# scary_rubber.net
KiCad netlist of a schematic drawn in EAGLE
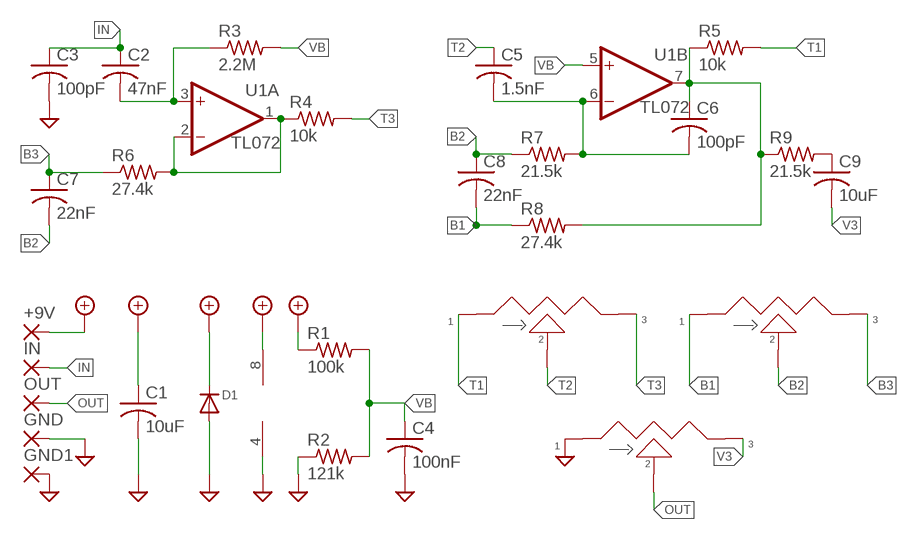
[diagram p0: schematic, sheet 1]

(export (version "E")
  (design (tool "Eeschema 10.0.6"))
  (components
    (comp (ref "+9V")
      (value "SMD2")
      (footprint "eagle-import:SMD1,27-2,54")
      (libsource (lib "eagle-import") (part "SMD2"))
    )
    (comp (ref "BASS")
      (value "B100k")
      (footprint "eagle-import:POT_9MM_SMD")
      (libsource (lib "eagle-import") (part "POT_9MM_SMD"))
    )
    (comp (ref "C1")
      (value "10uF")
      (footprint "eagle-import:C1206")
      (libsource (lib "eagle-import") (part "adafruit_420_C-USC1206"))
    )
    (comp (ref "C2")
      (value "47nF")
      (footprint "eagle-import:C0603")
      (libsource (lib "eagle-import") (part "C-USC0603"))
    )
    (comp (ref "C3")
      (value "100pF")
      (footprint "eagle-import:C0603")
      (libsource (lib "eagle-import") (part "C-USC0603"))
    )
    (comp (ref "C4")
      (value "100nF")
      (footprint "eagle-import:C0603")
      (libsource (lib "eagle-import") (part "C-USC0603"))
    )
    (comp (ref "C5")
      (value "1.5nF")
      (footprint "eagle-import:C0603")
      (libsource (lib "eagle-import") (part "C-USC0603"))
    )
    (comp (ref "C6")
      (value "100pF")
      (footprint "eagle-import:C0603")
      (libsource (lib "eagle-import") (part "C-USC0603"))
    )
    (comp (ref "C7")
      (value "22nF")
      (footprint "eagle-import:C0603")
      (libsource (lib "eagle-import") (part "C-USC0603"))
    )
    (comp (ref "C8")
      (value "22nF")
      (footprint "eagle-import:C0603")
      (libsource (lib "eagle-import") (part "C-USC0603"))
    )
    (comp (ref "C9")
      (value "10uF")
      (footprint "eagle-import:C1206")
      (libsource (lib "eagle-import") (part "adafruit_420_C-USC1206"))
    )
    (comp (ref "D1")
      (value "DIODESOD-123")
      (footprint "eagle-import:SOD-123")
      (libsource (lib "eagle-import") (part "DIODESOD-123"))
    )
    (comp (ref "GND")
      (value "SMD2")
      (footprint "eagle-import:SMD1,27-2,54")
      (libsource (lib "eagle-import") (part "SMD2"))
    )
    (comp (ref "GND1")
      (value "SMD2")
      (footprint "eagle-import:SMD1,27-2,54")
      (libsource (lib "eagle-import") (part "SMD2"))
    )
    (comp (ref "IN")
      (value "SMD2")
      (footprint "eagle-import:SMD1,27-2,54")
      (libsource (lib "eagle-import") (part "SMD2"))
    )
    (comp (ref "OUT")
      (value "SMD2")
      (footprint "eagle-import:SMD1,27-2,54")
      (libsource (lib "eagle-import") (part "SMD2"))
    )
    (comp (ref "R1")
      (value "100k")
      (footprint "eagle-import:R0603")
      (libsource (lib "eagle-import") (part "R-US_R0603"))
    )
    (comp (ref "R2")
      (value "121k")
      (footprint "eagle-import:R0603")
      (libsource (lib "eagle-import") (part "R-US_R0603"))
    )
    (comp (ref "R3")
      (value "2.2M")
      (footprint "eagle-import:R0603")
      (libsource (lib "eagle-import") (part "R-US_R0603"))
    )
    (comp (ref "R4")
      (value "10k")
      (footprint "eagle-import:R0603")
      (libsource (lib "eagle-import") (part "R-US_R0603"))
    )
    (comp (ref "R5")
      (value "10k")
      (footprint "eagle-import:R0603")
      (libsource (lib "eagle-import") (part "R-US_R0603"))
    )
    (comp (ref "R6")
      (value "27.4k")
      (footprint "eagle-import:R0603")
      (libsource (lib "eagle-import") (part "R-US_R0603"))
    )
    (comp (ref "R7")
      (value "21.5k")
      (footprint "eagle-import:R0603")
      (libsource (lib "eagle-import") (part "R-US_R0603"))
    )
    (comp (ref "R8")
      (value "27.4k")
      (footprint "eagle-import:R0603")
      (libsource (lib "eagle-import") (part "R-US_R0603"))
    )
    (comp (ref "R9")
      (value "21.5k")
      (footprint "eagle-import:R0603")
      (libsource (lib "eagle-import") (part "R-US_R0603"))
    )
    (comp (ref "TREB")
      (value "B100k")
      (footprint "eagle-import:POT_9MM_SMD")
      (libsource (lib "eagle-import") (part "POT_9MM_SMD"))
    )
    (comp (ref "U1")
      (value "TL072")
      (footprint "eagle-import:TSSOP-8")
      (libsource (lib "eagle-import") (part "TL072TSSOP"))
    )
    (comp (ref "VOLU")
      (value "B100k")
      (footprint "eagle-import:POT_9MM_SMD")
      (libsource (lib "eagle-import") (part "POT_9MM_SMD"))
    )
  )
  (nets
    (net (code "1") (name "+9V") (class "Default")
      (node (ref "+9V") (pin "1") (pinfunction "P_1") (pintype "passive"))
      (node (ref "C1") (pin "1") (pinfunction "1_1") (pintype "passive"))
      (node (ref "D1") (pin "C") (pinfunction "C_C") (pintype "passive"))
      (node (ref "R1") (pin "1") (pinfunction "1_1") (pintype "passive"))
      (node (ref "U1") (pin "8") (pinfunction "V+_8") (pintype "power_in"))
    )
    (net (code "2") (name "B1") (class "Default")
      (node (ref "BASS") (pin "1") (pinfunction "1_1") (pintype "bidirectional"))
      (node (ref "C8") (pin "2") (pinfunction "2_2") (pintype "passive"))
      (node (ref "R8") (pin "1") (pinfunction "1_1") (pintype "passive"))
    )
    (net (code "3") (name "B2") (class "Default")
      (node (ref "BASS") (pin "2") (pinfunction "2_2") (pintype "bidirectional"))
      (node (ref "C7") (pin "2") (pinfunction "2_2") (pintype "passive"))
      (node (ref "C8") (pin "1") (pinfunction "1_1") (pintype "passive"))
      (node (ref "R7") (pin "1") (pinfunction "1_1") (pintype "passive"))
    )
    (net (code "4") (name "B3") (class "Default")
      (node (ref "BASS") (pin "3") (pinfunction "3_3") (pintype "bidirectional"))
      (node (ref "C7") (pin "1") (pinfunction "1_1") (pintype "passive"))
      (node (ref "R6") (pin "1") (pinfunction "1_1") (pintype "passive"))
    )
    (net (code "5") (name "GND") (class "Default")
      (node (ref "C1") (pin "2") (pinfunction "2_2") (pintype "passive"))
      (node (ref "C3") (pin "2") (pinfunction "2_2") (pintype "passive"))
      (node (ref "C4") (pin "2") (pinfunction "2_2") (pintype "passive"))
      (node (ref "D1") (pin "A") (pinfunction "A_A") (pintype "passive"))
      (node (ref "GND") (pin "1") (pinfunction "P_1") (pintype "passive"))
      (node (ref "GND1") (pin "1") (pinfunction "P_1") (pintype "passive"))
      (node (ref "R2") (pin "1") (pinfunction "1_1") (pintype "passive"))
      (node (ref "U1") (pin "4") (pinfunction "V-_4") (pintype "power_in"))
      (node (ref "VOLU") (pin "1") (pinfunction "1_1") (pintype "bidirectional"))
    )
    (net (code "6") (name "IN") (class "Default")
      (node (ref "C2") (pin "1") (pinfunction "1_1") (pintype "passive"))
      (node (ref "C3") (pin "1") (pinfunction "1_1") (pintype "passive"))
      (node (ref "IN") (pin "1") (pinfunction "P_1") (pintype "passive"))
    )
    (net (code "7") (name "Net-(C9-Pad1)") (class "Default")
      (node (ref "C9") (pin "1") (pinfunction "1_1") (pintype "passive"))
      (node (ref "R9") (pin "2") (pinfunction "2_2") (pintype "passive"))
    )
    (net (code "8") (name "Net-(U1A-+IN)") (class "Default")
      (node (ref "C2") (pin "2") (pinfunction "2_2") (pintype "passive"))
      (node (ref "R3") (pin "1") (pinfunction "1_1") (pintype "passive"))
      (node (ref "U1") (pin "3") (pinfunction "+IN_3") (pintype "input"))
    )
    (net (code "9") (name "Net-(U1A--IN)") (class "Default")
      (node (ref "R4") (pin "1") (pinfunction "1_1") (pintype "passive"))
      (node (ref "R6") (pin "2") (pinfunction "2_2") (pintype "passive"))
      (node (ref "U1") (pin "1") (pinfunction "OUT_1") (pintype "output"))
      (node (ref "U1") (pin "2") (pinfunction "-IN_2") (pintype "input"))
    )
    (net (code "10") (name "Net-(U1B--IN)") (class "Default")
      (node (ref "C5") (pin "2") (pinfunction "2_2") (pintype "passive"))
      (node (ref "C6") (pin "2") (pinfunction "2_2") (pintype "passive"))
      (node (ref "R7") (pin "2") (pinfunction "2_2") (pintype "passive"))
      (node (ref "U1") (pin "6") (pinfunction "-IN_6") (pintype "input"))
    )
    (net (code "11") (name "Net-(U1B-OUT)") (class "Default")
      (node (ref "C6") (pin "1") (pinfunction "1_1") (pintype "passive"))
      (node (ref "R5") (pin "1") (pinfunction "1_1") (pintype "passive"))
      (node (ref "R8") (pin "2") (pinfunction "2_2") (pintype "passive"))
      (node (ref "R9") (pin "1") (pinfunction "1_1") (pintype "passive"))
      (node (ref "U1") (pin "7") (pinfunction "OUT_7") (pintype "output"))
    )
    (net (code "12") (name "OUT") (class "Default")
      (node (ref "OUT") (pin "1") (pinfunction "P_1") (pintype "passive"))
      (node (ref "VOLU") (pin "2") (pinfunction "2_2") (pintype "bidirectional"))
    )
    (net (code "13") (name "T1") (class "Default")
      (node (ref "R5") (pin "2") (pinfunction "2_2") (pintype "passive"))
      (node (ref "TREB") (pin "1") (pinfunction "1_1") (pintype "bidirectional"))
    )
    (net (code "14") (name "T2") (class "Default")
      (node (ref "C5") (pin "1") (pinfunction "1_1") (pintype "passive"))
      (node (ref "TREB") (pin "2") (pinfunction "2_2") (pintype "bidirectional"))
    )
    (net (code "15") (name "T3") (class "Default")
      (node (ref "R4") (pin "2") (pinfunction "2_2") (pintype "passive"))
      (node (ref "TREB") (pin "3") (pinfunction "3_3") (pintype "bidirectional"))
    )
    (net (code "16") (name "V3") (class "Default")
      (node (ref "C9") (pin "2") (pinfunction "2_2") (pintype "passive"))
      (node (ref "VOLU") (pin "3") (pinfunction "3_3") (pintype "bidirectional"))
    )
    (net (code "17") (name "VB") (class "Default")
      (node (ref "C4") (pin "1") (pinfunction "1_1") (pintype "passive"))
      (node (ref "R1") (pin "2") (pinfunction "2_2") (pintype "passive"))
      (node (ref "R2") (pin "2") (pinfunction "2_2") (pintype "passive"))
      (node (ref "R3") (pin "2") (pinfunction "2_2") (pintype "passive"))
      (node (ref "U1") (pin "5") (pinfunction "+IN_5") (pintype "input"))
    )
  )
)
